# microcontroller.net
KiCad netlist of a schematic drawn in Altium Designer
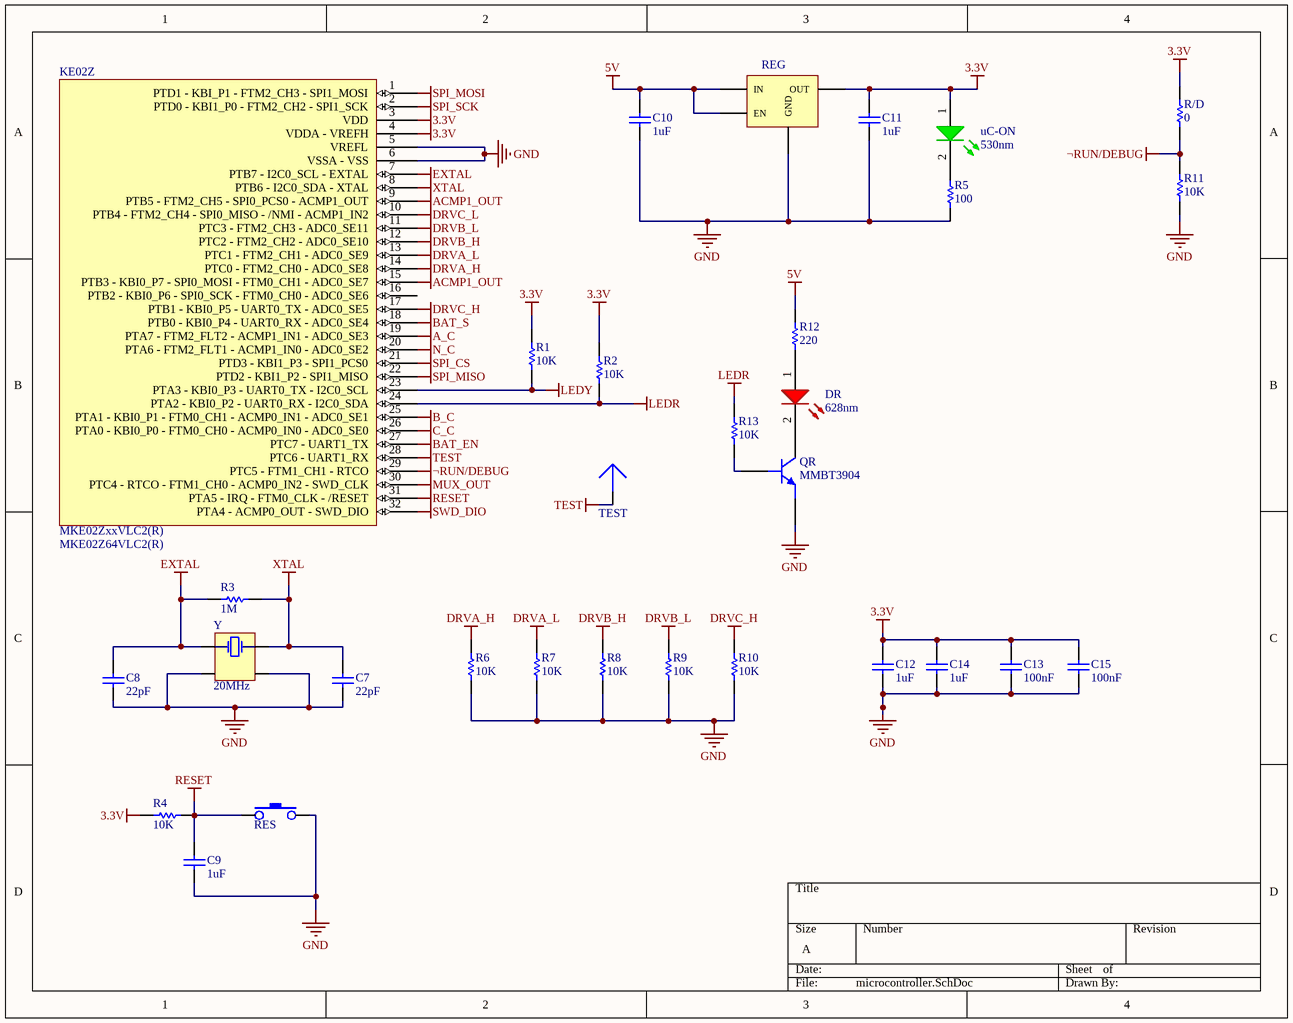
[diagram p0: microcontroller.SchDoc]

(export (version "E")
  (design (tool "Eeschema 10.0.6"))
  (components
    (comp (ref "C7")
      (value "22pF")
      (footprint "CAPC1608L")
      (description "CAP CER 22PF 50V 5% NP0 0603")
      (fields (field (name "MANUFACTURER PART NUMBER") "CL10C220JB8NCNC"))
      (libsource (lib "flxlib") (part "CAP-NO_POL"))
    )
    (comp (ref "C8")
      (value "22pF")
      (footprint "CAPC1608L")
      (description "CAP CER 22PF 50V 5% NP0 0603")
      (fields (field (name "MANUFACTURER PART NUMBER") "CL10C220JB8NCNC"))
      (libsource (lib "flxlib") (part "CAP-NO_POL"))
    )
    (comp (ref "C9")
      (value "1uF")
      (footprint "CAPC1608L")
      (description "CAP CER 1UF 25V 10% X5R 0603")
      (fields (field (name "MANUFACTURER PART NUMBER") "TMK107BJ105KA-T"))
      (libsource (lib "flxlib") (part "CAP-NO_POL"))
    )
    (comp (ref "C10")
      (value "1uF")
      (footprint "CAPC1608L")
      (description "CAP CER 1UF 25V 10% X5R 0603")
      (fields (field (name "MANUFACTURER PART NUMBER") "TMK107BJ105KA-T"))
      (libsource (lib "flxlib") (part "CAP-NO_POL"))
    )
    (comp (ref "C11")
      (value "1uF")
      (footprint "CAPC1608L")
      (description "CAP CER 1UF 25V 10% X5R 0603")
      (fields (field (name "MANUFACTURER PART NUMBER") "TMK107BJ105KA-T"))
      (libsource (lib "flxlib") (part "CAP-NO_POL"))
    )
    (comp (ref "C12")
      (value "1uF")
      (footprint "CAPC1608L")
      (description "CAP CER 1UF 25V 10% X5R 0603")
      (fields (field (name "MANUFACTURER PART NUMBER") "TMK107BJ105KA-T"))
      (libsource (lib "flxlib") (part "CAP-NO_POL"))
    )
    (comp (ref "C13")
      (value "100nF")
      (footprint "CAPC1608L")
      (description "CAP CER 0.1UF 50V Y5V 0603")
      (fields (field (name "MANUFACTURER PART NUMBER") "CC0603ZRY5V9BB104"))
      (libsource (lib "flxlib") (part "CAP-NO_POL"))
    )
    (comp (ref "C14")
      (value "1uF")
      (footprint "CAPC1608L")
      (description "CAP CER 1UF 25V 10% X5R 0603")
      (fields (field (name "MANUFACTURER PART NUMBER") "TMK107BJ105KA-T"))
      (libsource (lib "flxlib") (part "CAP-NO_POL"))
    )
    (comp (ref "C15")
      (value "100nF")
      (footprint "CAPC1608L")
      (description "CAP CER 0.1UF 50V Y5V 0603")
      (fields (field (name "MANUFACTURER PART NUMBER") "CC0603ZRY5V9BB104"))
      (libsource (lib "flxlib") (part "CAP-NO_POL"))
    )
    (comp (ref "DR")
      (value "628nm")
      (footprint "DSO-F2/D3.4")
      (description "LED POINTLED 628NM SUPER RED SMD")
      (fields
        (field (name "MANUFACTURER") "OSRAM Opto Semiconductors Inc")
        (field (name "MANUFACTURER PART NUMBER") "LS Q971-KN-1")
        (field (name "DRAWN BY") "Juan I Carrano")
      )
      (libsource (lib "flxlib") (part "LED-RED"))
    )
    (comp (ref "KE02Z")
      (value "MKE02ZxxVLC2(R)")
      (footprint "JEDEC_MS-026BBA")
      (description "Kinetis KE02 Cortex®-M0+ MCU 32 Pin LQFP")
      (fields
        (field (name "MANUFACTURER PART NUMBER") "MKE02Z64VLC2(R)")
        (field (name "MANUFACTURER") "Freescale")
      )
      (libsource (lib "flxlib") (part "MKE02ZxxVLC2(R)"))
    )
    (comp (ref "QR")
      (value "MMBT3904")
      (footprint "SOT23-3L")
      (description "TRANSISTOR NPN 40V 0.2A SOT23")
      (fields (field (name "MANUFACTURER") "NXP Semiconductors") (field (name "Comment") "BJT-NPN-BEC"))
      (libsource (lib "flxlib") (part "BJT-NPN-BEC"))
    )
    (comp (ref "R/D")
      (value "0")
      (footprint "RESC1608L")
      (description "RES 0.0 OHM 1/10W JUMP 0603")
      (fields (field (name "MANUFACTURER PART NUMBER") "RC1608J000CS"))
      (libsource (lib "flxlib") (part "RES-0"))
    )
    (comp (ref "R1")
      (value "10K")
      (footprint "RESC1608L")
      (description "RES 10K OHM 1/10W 5% 0603")
      (fields (field (name "MANUFACTURER PART NUMBER") "RC1608J103CS"))
      (libsource (lib "flxlib") (part "RES"))
    )
    (comp (ref "R2")
      (value "10K")
      (footprint "RESC1608L")
      (description "RES 10K OHM 1/10W 5% 0603")
      (fields (field (name "MANUFACTURER PART NUMBER") "RC1608J103CS"))
      (libsource (lib "flxlib") (part "RES"))
    )
    (comp (ref "R3")
      (value "1M")
      (footprint "RESC1608L")
      (description "RES 1.00M OHM 1/10W 1% 0603 SMD")
      (fields
        (field (name "MANUFACTURER") "Yageo")
        (field (name "MANUFACTURER PART NUMBER") "RC0603FR-071ML")
      )
      (libsource (lib "flxlib") (part "RES"))
    )
    (comp (ref "R4")
      (value "10K")
      (footprint "RESC1608L")
      (description "RES 10K OHM 1/10W 5% 0603")
      (fields (field (name "MANUFACTURER PART NUMBER") "RC1608J103CS"))
      (libsource (lib "flxlib") (part "RES"))
    )
    (comp (ref "R5")
      (value "100")
      (footprint "RESC1608L")
      (description "RES 100 OHM 1/10W 5% 0603 SMD")
      (fields (field (name "MANUFACTURER PART NUMBER") "RC0603JR-07100RL"))
      (libsource (lib "flxlib") (part "RES"))
    )
    (comp (ref "R6")
      (value "10K")
      (footprint "RESC1608L")
      (description "RES 10K OHM 1/10W 5% 0603")
      (fields (field (name "MANUFACTURER PART NUMBER") "RC1608J103CS"))
      (libsource (lib "flxlib") (part "RES"))
    )
    (comp (ref "R7")
      (value "10K")
      (footprint "RESC1608L")
      (description "RES 10K OHM 1/10W 5% 0603")
      (fields (field (name "MANUFACTURER PART NUMBER") "RC1608J103CS"))
      (libsource (lib "flxlib") (part "RES"))
    )
    (comp (ref "R8")
      (value "10K")
      (footprint "RESC1608L")
      (description "RES 10K OHM 1/10W 5% 0603")
      (fields (field (name "MANUFACTURER PART NUMBER") "RC1608J103CS"))
      (libsource (lib "flxlib") (part "RES"))
    )
    (comp (ref "R9")
      (value "10K")
      (footprint "RESC1608L")
      (description "RES 10K OHM 1/10W 5% 0603")
      (fields (field (name "MANUFACTURER PART NUMBER") "RC1608J103CS"))
      (libsource (lib "flxlib") (part "RES"))
    )
    (comp (ref "R10")
      (value "10K")
      (footprint "RESC1608L")
      (description "RES 10K OHM 1/10W 5% 0603")
      (fields (field (name "MANUFACTURER PART NUMBER") "RC1608J103CS"))
      (libsource (lib "flxlib") (part "RES"))
    )
    (comp (ref "R11")
      (value "10K")
      (footprint "RESC1608L")
      (description "RES 10K OHM 1/10W 5% 0603")
      (fields (field (name "MANUFACTURER PART NUMBER") "RC1608J103CS"))
      (libsource (lib "flxlib") (part "RES"))
    )
    (comp (ref "R12")
      (value "220")
      (footprint "RESC1608L")
      (description "RES 100 OHM 1/10W 5% 0603 SMD")
      (fields (field (name "MANUFACTURER PART NUMBER") "RC0603JR-07100RL"))
      (libsource (lib "flxlib") (part "RES"))
    )
    (comp (ref "R13")
      (value "10K")
      (footprint "RESC1608L")
      (description "RES 10K OHM 1/10W 5% 0603")
      (fields (field (name "MANUFACTURER PART NUMBER") "RC1608J103CS"))
      (libsource (lib "flxlib") (part "RES"))
    )
    (comp (ref "REG")
      (value "LP5900")
      (footprint "x-TI_S-NGF0006A")
      (description "IC REG LDO 3.3V 0.15A 6WSON")
      (fields
        (field (name "MANUFACTURER") "Texas Instruments")
        (field (name "MANUFACTURER PART NUMBER") "LP5900SD-3.3/NOPB")
      )
      (libsource (lib "flxlib") (part "LREG_4T_6pinA_3.3V"))
    )
    (comp (ref "RES")
      (value "SWITCH_TACTILE_SPST-2T-NO")
      (footprint "X-TECO_FSMSM")
      (description "SWITCH TACTILE SPST-NO 0.05A 12V")
      (fields
        (field (name "MANUFACTURER") "TE Connectivity")
        (field (name "MANUFACTURER PART NUMBER") "FSMSM")
      )
      (libsource (lib "flxlib") (part "SWITCH_TACTILE_SPST-2T-NO"))
    )
    (comp (ref "TEST")
      (value "TESTPOINT-ARROW-BLUE")
      (footprint "TESTP_PAD_.75mm")
      (description "Round Test Point on Board")
      (libsource (lib "flxlib") (part "TESTPOINT-ARROW-BLUE"))
    )
    (comp (ref "uC-ON")
      (value "530nm")
      (footprint "DSO-F2/D3.4")
      (description "LED CHIPLED 570NM GREEN 0603 SMD")
      (fields
        (field (name "MANUFACTURER") "OSRAM Opto Semiconductors Inc")
        (field (name "MANUFACTURER PART NUMBER") "LG Q971-KN-1")
        (field (name "DRAWN BY") "Juan I Carrano")
      )
      (libsource (lib "flxlib") (part "LED-GREEN"))
    )
    (comp (ref "Y")
      (value "20MHz")
      (footprint "X-EPSO_TSX-3225")
      (description "CRYSTAL 20MHZ 9PF SMD")
      (fields
        (field (name "MANUFACTURER") "EPSON")
        (field (name "MANUFACTURER PART NUMBER") "TSX-3225 20.0000MF20G-AC3")
        (field (name "DRAWN BY") "Juan I Carrano")
      )
      (libsource (lib "flxlib") (part "XTAL-4T"))
    )
  )
  (nets
    (net (code "1") (name "3.3V") (class "Default")
      (node (ref "C11") (pin "1") (pinfunction "1_1") (pintype "passive"))
      (node (ref "C12") (pin "1") (pinfunction "1_1") (pintype "passive"))
      (node (ref "C13") (pin "1") (pinfunction "1_1") (pintype "passive"))
      (node (ref "C14") (pin "1") (pinfunction "1_1") (pintype "passive"))
      (node (ref "C15") (pin "1") (pinfunction "1_1") (pintype "passive"))
      (node (ref "KE02Z") (pin "3") (pinfunction "VDD_3") (pintype "passive"))
      (node (ref "KE02Z") (pin "4") (pinfunction "VDDA_-_VREFH_4") (pintype "passive"))
      (node (ref "R/D") (pin "1") (pinfunction "1_1") (pintype "passive"))
      (node (ref "R1") (pin "1") (pinfunction "1_1") (pintype "passive"))
      (node (ref "R2") (pin "1") (pinfunction "1_1") (pintype "passive"))
      (node (ref "R4") (pin "1") (pinfunction "1_1") (pintype "passive"))
      (node (ref "REG") (pin "1") (pinfunction "OUT_1") (pintype "passive"))
      (node (ref "uC-ON") (pin "1") (pinfunction "A_1") (pintype "passive"))
    )
    (net (code "2") (name "5V") (class "Default")
      (node (ref "C10") (pin "1") (pinfunction "1_1") (pintype "passive"))
      (node (ref "R12") (pin "1") (pinfunction "1_1") (pintype "passive"))
      (node (ref "REG") (pin "4") (pinfunction "EN_4") (pintype "passive"))
      (node (ref "REG") (pin "6") (pinfunction "IN_6") (pintype "passive"))
    )
    (net (code "3") (name "ACMP1_OUT") (class "Default")
      (node (ref "KE02Z") (pin "15") (pinfunction "PTB3_-_KBI0_P7_-_SPI0_MOSI_-_FTM0_CH1_-_ADC0_SE7_15") (pintype "bidirectional"))
      (node (ref "KE02Z") (pin "9") (pinfunction "PTB5_-_FTM2_CH5_-_SPI0_PCS0_-_ACMP1_OUT_9") (pintype "bidirectional"))
    )
    (net (code "4") (name "A_C") (class "Default")
      (node (ref "KE02Z") (pin "19") (pinfunction "PTA7_-_FTM2_FLT2_-_ACMP1_IN1_-_ADC0_SE3_19") (pintype "bidirectional"))
    )
    (net (code "5") (name "BAT_EN") (class "Default")
      (node (ref "KE02Z") (pin "27") (pinfunction "PTC7_-_UART1_TX_27") (pintype "bidirectional"))
    )
    (net (code "6") (name "BAT_S") (class "Default")
      (node (ref "KE02Z") (pin "18") (pinfunction "PTB0_-_KBI0_P4_-_UART0_RX_-_ADC0_SE4_18") (pintype "bidirectional"))
    )
    (net (code "7") (name "B_C") (class "Default")
      (node (ref "KE02Z") (pin "25") (pinfunction "PTA1_-_KBI0_P1_-_FTM0_CH1_-_ACMP0_IN1_-_ADC0_SE1_25") (pintype "bidirectional"))
    )
    (net (code "8") (name "C_C") (class "Default")
      (node (ref "KE02Z") (pin "26") (pinfunction "PTA0_-_KBI0_P0_-_FTM0_CH0_-_ACMP0_IN0_-_ADC0_SE0_26") (pintype "bidirectional"))
    )
    (net (code "9") (name "DRVA_H") (class "Default")
      (node (ref "KE02Z") (pin "14") (pinfunction "PTC0_-_FTM2_CH0_-_ADC0_SE8_14") (pintype "bidirectional"))
      (node (ref "R6") (pin "1") (pinfunction "1_1") (pintype "passive"))
    )
    (net (code "10") (name "DRVA_L") (class "Default")
      (node (ref "KE02Z") (pin "13") (pinfunction "PTC1_-_FTM2_CH1_-_ADC0_SE9_13") (pintype "bidirectional"))
      (node (ref "R7") (pin "1") (pinfunction "1_1") (pintype "passive"))
    )
    (net (code "11") (name "DRVB_H") (class "Default")
      (node (ref "KE02Z") (pin "12") (pinfunction "PTC2_-_FTM2_CH2_-_ADC0_SE10_12") (pintype "bidirectional"))
      (node (ref "R8") (pin "1") (pinfunction "1_1") (pintype "passive"))
    )
    (net (code "12") (name "DRVB_L") (class "Default")
      (node (ref "KE02Z") (pin "11") (pinfunction "PTC3_-_FTM2_CH3_-_ADC0_SE11_11") (pintype "bidirectional"))
      (node (ref "R9") (pin "1") (pinfunction "1_1") (pintype "passive"))
    )
    (net (code "13") (name "DRVC_H") (class "Default")
      (node (ref "KE02Z") (pin "17") (pinfunction "PTB1_-_KBI0_P5_-_UART0_TX_-_ADC0_SE5_17") (pintype "bidirectional"))
      (node (ref "R10") (pin "1") (pinfunction "1_1") (pintype "passive"))
    )
    (net (code "14") (name "DRVC_L") (class "Default")
      (node (ref "KE02Z") (pin "10") (pinfunction "PTB4_-_FTM2_CH4_-_SPI0_MISO_-_/NMI_-_ACMP1_IN2_10") (pintype "bidirectional"))
    )
    (net (code "15") (name "EXTAL") (class "Default")
      (node (ref "C8") (pin "1") (pinfunction "1_1") (pintype "passive"))
      (node (ref "KE02Z") (pin "7") (pinfunction "PTB7_-_I2C0_SCL_-_EXTAL_7") (pintype "bidirectional"))
      (node (ref "R3") (pin "2") (pinfunction "2_2") (pintype "passive"))
      (node (ref "Y") (pin "1") (pinfunction "1_1") (pintype "passive"))
    )
    (net (code "16") (name "GND") (class "Default")
      (node (ref "C10") (pin "2") (pinfunction "2_2") (pintype "passive"))
      (node (ref "C11") (pin "2") (pinfunction "2_2") (pintype "passive"))
      (node (ref "C12") (pin "2") (pinfunction "2_2") (pintype "passive"))
      (node (ref "C13") (pin "2") (pinfunction "2_2") (pintype "passive"))
      (node (ref "C14") (pin "2") (pinfunction "2_2") (pintype "passive"))
      (node (ref "C15") (pin "2") (pinfunction "2_2") (pintype "passive"))
      (node (ref "C7") (pin "2") (pinfunction "2_2") (pintype "passive"))
      (node (ref "C8") (pin "2") (pinfunction "2_2") (pintype "passive"))
      (node (ref "C9") (pin "2") (pinfunction "2_2") (pintype "passive"))
      (node (ref "KE02Z") (pin "5") (pinfunction "VREFL_5") (pintype "passive"))
      (node (ref "KE02Z") (pin "6") (pinfunction "VSSA_-_VSS_6") (pintype "passive"))
      (node (ref "QR") (pin "2") (pinfunction "E_2") (pintype "passive"))
      (node (ref "R10") (pin "2") (pinfunction "2_2") (pintype "passive"))
      (node (ref "R11") (pin "2") (pinfunction "2_2") (pintype "passive"))
      (node (ref "R5") (pin "2") (pinfunction "2_2") (pintype "passive"))
      (node (ref "R6") (pin "2") (pinfunction "2_2") (pintype "passive"))
      (node (ref "R7") (pin "2") (pinfunction "2_2") (pintype "passive"))
      (node (ref "R8") (pin "2") (pinfunction "2_2") (pintype "passive"))
      (node (ref "R9") (pin "2") (pinfunction "2_2") (pintype "passive"))
      (node (ref "REG") (pin "3") (pinfunction "GND_3") (pintype "passive"))
      (node (ref "RES") (pin "2") (pinfunction "2_2") (pintype "passive"))
      (node (ref "Y") (pin "2") (pinfunction "2_2") (pintype "passive"))
      (node (ref "Y") (pin "4") (pinfunction "4_4") (pintype "passive"))
    )
    (net (code "17") (name "LEDR") (class "Default")
      (node (ref "KE02Z") (pin "24") (pinfunction "PTA2_-_KBI0_P2_-_UART0_RX_-_I2C0_SDA_24") (pintype "bidirectional"))
      (node (ref "R13") (pin "2") (pinfunction "2_2") (pintype "passive"))
      (node (ref "R2") (pin "2") (pinfunction "2_2") (pintype "passive"))
    )
    (net (code "18") (name "LEDY") (class "Default")
      (node (ref "KE02Z") (pin "23") (pinfunction "PTA3_-_KBI0_P3_-_UART0_TX_-_I2C0_SCL_23") (pintype "bidirectional"))
      (node (ref "R1") (pin "2") (pinfunction "2_2") (pintype "passive"))
    )
    (net (code "19") (name "MUX_OUT") (class "Default")
      (node (ref "KE02Z") (pin "30") (pinfunction "PTC4_-_RTCO_-_FTM1_CH0_-_ACMP0_IN2_-_SWD_CLK_30") (pintype "bidirectional"))
    )
    (net (code "20") (name "N_C") (class "Default")
      (node (ref "KE02Z") (pin "20") (pinfunction "PTA6_-_FTM2_FLT1_-_ACMP1_IN0_-_ADC0_SE2_20") (pintype "bidirectional"))
    )
    (net (code "21") (name "Net-(DR-A)") (class "Default")
      (node (ref "DR") (pin "1") (pinfunction "A_1") (pintype "passive"))
      (node (ref "R12") (pin "2") (pinfunction "2_2") (pintype "passive"))
    )
    (net (code "22") (name "Net-(DR-K)") (class "Default")
      (node (ref "DR") (pin "2") (pinfunction "K_2") (pintype "passive"))
      (node (ref "QR") (pin "3") (pinfunction "C_3") (pintype "passive"))
    )
    (net (code "23") (name "Net-(QR-B)") (class "Default")
      (node (ref "QR") (pin "1") (pinfunction "B_1") (pintype "passive"))
      (node (ref "R13") (pin "1") (pinfunction "1_1") (pintype "passive"))
    )
    (net (code "24") (name "Net-(uC-ON-K)") (class "Default")
      (node (ref "R5") (pin "1") (pinfunction "1_1") (pintype "passive"))
      (node (ref "uC-ON") (pin "2") (pinfunction "K_2") (pintype "passive"))
    )
    (net (code "25") (name "RESET") (class "Default")
      (node (ref "C9") (pin "1") (pinfunction "1_1") (pintype "passive"))
      (node (ref "KE02Z") (pin "31") (pinfunction "PTA5_-_IRQ_-_FTM0_CLK_-_/RESET_31") (pintype "bidirectional"))
      (node (ref "R4") (pin "2") (pinfunction "2_2") (pintype "passive"))
      (node (ref "RES") (pin "1") (pinfunction "1_1") (pintype "passive"))
    )
    (net (code "26") (name "SPI_CS") (class "Default")
      (node (ref "KE02Z") (pin "21") (pinfunction "PTD3_-_KBI1_P3_-_SPI1_PCS0_21") (pintype "bidirectional"))
    )
    (net (code "27") (name "SPI_MISO") (class "Default")
      (node (ref "KE02Z") (pin "22") (pinfunction "PTD2_-_KBI1_P2_-_SPI1_MISO_22") (pintype "bidirectional"))
    )
    (net (code "28") (name "SPI_MOSI") (class "Default")
      (node (ref "KE02Z") (pin "1") (pinfunction "PTD1_-_KBI_P1_-_FTM2_CH3_-_SPI1_MOSI_1") (pintype "bidirectional"))
    )
    (net (code "29") (name "SPI_SCK") (class "Default")
      (node (ref "KE02Z") (pin "2") (pinfunction "PTD0_-_KBI1_P0_-_FTM2_CH2_-_SPI1_SCK_2") (pintype "bidirectional"))
    )
    (net (code "30") (name "SWD_DIO") (class "Default")
      (node (ref "KE02Z") (pin "32") (pinfunction "PTA4_-_ACMP0_OUT_-_SWD_DIO_32") (pintype "bidirectional"))
    )
    (net (code "31") (name "TEST") (class "Default")
      (node (ref "KE02Z") (pin "28") (pinfunction "PTC6_-_UART1_RX_28") (pintype "bidirectional"))
      (node (ref "TEST") (pin "1") (pinfunction "1_1") (pintype "passive"))
    )
    (net (code "32") (name "XTAL") (class "Default")
      (node (ref "C7") (pin "1") (pinfunction "1_1") (pintype "passive"))
      (node (ref "KE02Z") (pin "8") (pinfunction "PTB6_-_I2C0_SDA_-_XTAL_8") (pintype "bidirectional"))
      (node (ref "R3") (pin "1") (pinfunction "1_1") (pintype "passive"))
      (node (ref "Y") (pin "3") (pinfunction "3_3") (pintype "passive"))
    )
    (net (code "33") (name "unconnected-(KE02Z-PTB2_-_KBI0_P6_-_SPI0_SCK_-_FTM0_CH0_-_ADC0_SE6-Pad16)") (class "Default")
      (node (ref "KE02Z") (pin "16") (pinfunction "PTB2_-_KBI0_P6_-_SPI0_SCK_-_FTM0_CH0_-_ADC0_SE6_16") (pintype "bidirectional"))
    )
    (net (code "34") (name "¬RUN{slash}DEBUG") (class "Default")
      (node (ref "KE02Z") (pin "29") (pinfunction "PTC5_-_FTM1_CH1_-_RTCO_29") (pintype "bidirectional"))
      (node (ref "R/D") (pin "2") (pinfunction "2_2") (pintype "passive"))
      (node (ref "R11") (pin "1") (pinfunction "1_1") (pintype "passive"))
    )
  )
)
